# Shruthi-Analog-PoleMixing-v02.net
KiCad netlist of a schematic drawn in EAGLE
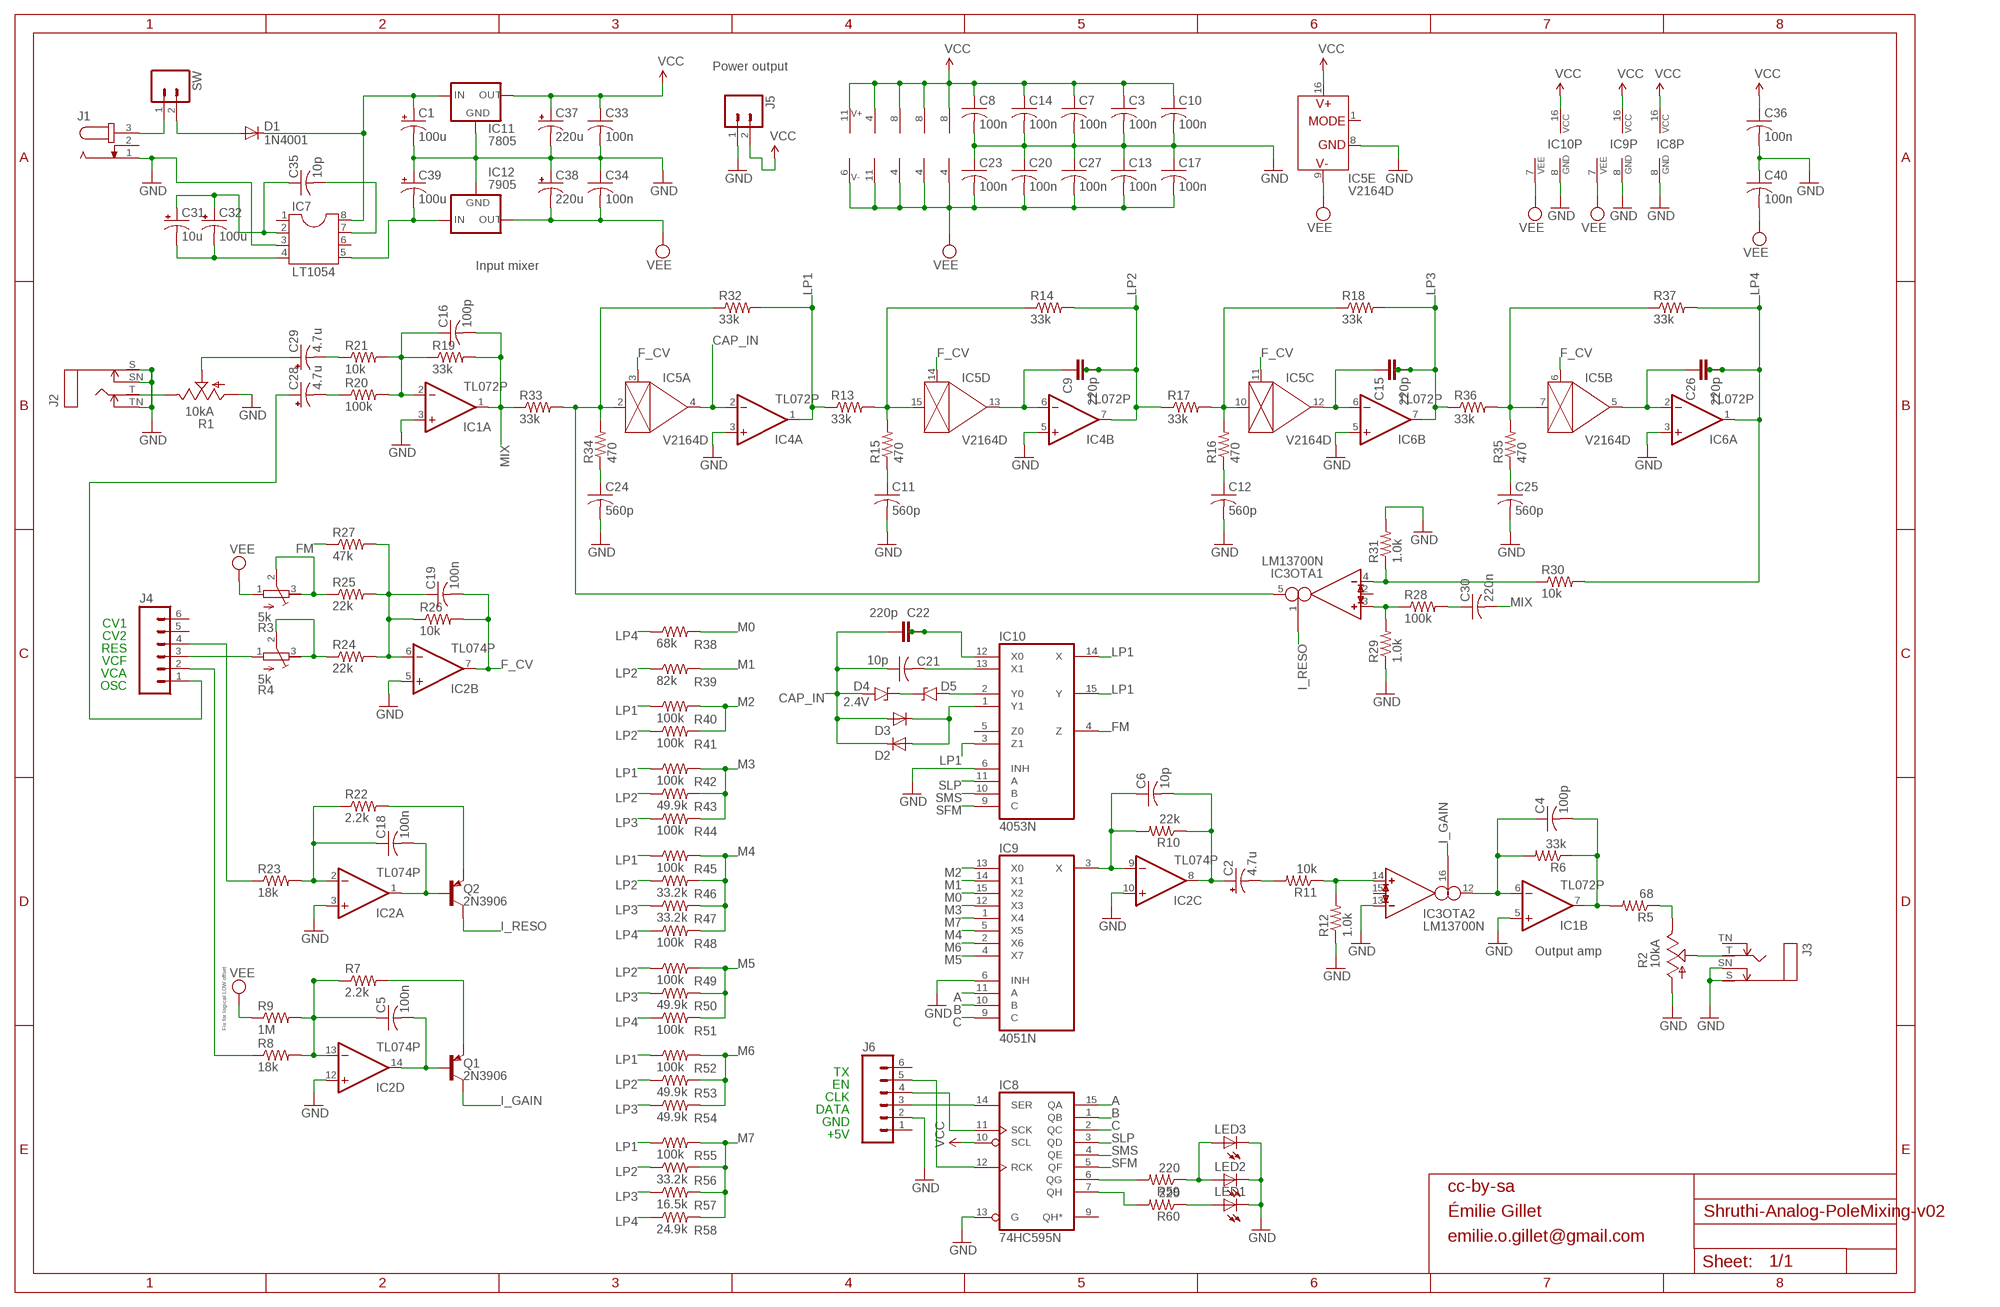
[diagram p0: schematic, sheet 1]

(export (version "E")
  (design (tool "Eeschema 10.0.6"))
  (components
    (comp (ref "C1")
      (value "100u")
      (footprint "eagle-import:E2,5-7")
      (libsource (lib "eagle-import") (part "CPOL-USE2.5-7"))
    )
    (comp (ref "C2")
      (value "4.7u")
      (footprint "eagle-import:E2,5-6")
      (libsource (lib "eagle-import") (part "CPOL-USE2.5-6"))
    )
    (comp (ref "C3")
      (value "100n")
      (footprint "eagle-import:C025-025X050")
      (libsource (lib "eagle-import") (part "C-US025-025X050"))
    )
    (comp (ref "C4")
      (value "100p")
      (footprint "eagle-import:C025-025X050")
      (libsource (lib "eagle-import") (part "C-US025-025X050"))
    )
    (comp (ref "C5")
      (value "100n")
      (footprint "eagle-import:C025-025X050")
      (libsource (lib "eagle-import") (part "C-US025-025X050"))
    )
    (comp (ref "C6")
      (value "10p")
      (footprint "eagle-import:C025-025X050")
      (libsource (lib "eagle-import") (part "C-US025-025X050"))
    )
    (comp (ref "C7")
      (value "100n")
      (footprint "eagle-import:C025-025X050")
      (libsource (lib "eagle-import") (part "C-US025-025X050"))
    )
    (comp (ref "C8")
      (value "100n")
      (footprint "eagle-import:C025-025X050")
      (libsource (lib "eagle-import") (part "C-US025-025X050"))
    )
    (comp (ref "C9")
      (value "220p")
      (footprint "eagle-import:C2.5_5-4")
      (libsource (lib "eagle-import") (part "C-2.5-5/4"))
    )
    (comp (ref "C10")
      (value "100n")
      (footprint "eagle-import:C025-025X050")
      (libsource (lib "eagle-import") (part "C-US025-025X050"))
    )
    (comp (ref "C11")
      (value "560p")
      (footprint "eagle-import:C025-025X050")
      (libsource (lib "eagle-import") (part "C-US025-025X050"))
    )
    (comp (ref "C12")
      (value "560p")
      (footprint "eagle-import:C025-025X050")
      (libsource (lib "eagle-import") (part "C-US025-025X050"))
    )
    (comp (ref "C13")
      (value "100n")
      (footprint "eagle-import:C025-025X050")
      (libsource (lib "eagle-import") (part "C-US025-025X050"))
    )
    (comp (ref "C14")
      (value "100n")
      (footprint "eagle-import:C025-025X050")
      (libsource (lib "eagle-import") (part "C-US025-025X050"))
    )
    (comp (ref "C15")
      (value "220p")
      (footprint "eagle-import:C2.5_5-4")
      (libsource (lib "eagle-import") (part "C-2.5-5/4"))
    )
    (comp (ref "C16")
      (value "100p")
      (footprint "eagle-import:C025-025X050")
      (libsource (lib "eagle-import") (part "C-US025-025X050"))
    )
    (comp (ref "C17")
      (value "100n")
      (footprint "eagle-import:C025-025X050")
      (libsource (lib "eagle-import") (part "C-US025-025X050"))
    )
    (comp (ref "C18")
      (value "100n")
      (footprint "eagle-import:C025-025X050")
      (libsource (lib "eagle-import") (part "C-US025-025X050"))
    )
    (comp (ref "C19")
      (value "100n")
      (footprint "eagle-import:C025-025X050")
      (libsource (lib "eagle-import") (part "C-US025-025X050"))
    )
    (comp (ref "C20")
      (value "100n")
      (footprint "eagle-import:C025-025X050")
      (libsource (lib "eagle-import") (part "C-US025-025X050"))
    )
    (comp (ref "C21")
      (value "10p")
      (footprint "eagle-import:C025-025X050")
      (libsource (lib "eagle-import") (part "C-US025-025X050"))
    )
    (comp (ref "C22")
      (value "220p")
      (footprint "eagle-import:C2.5_5-4")
      (libsource (lib "eagle-import") (part "C-2.5-5/4"))
    )
    (comp (ref "C23")
      (value "100n")
      (footprint "eagle-import:C025-025X050")
      (libsource (lib "eagle-import") (part "C-US025-025X050"))
    )
    (comp (ref "C24")
      (value "560p")
      (footprint "eagle-import:C025-025X050")
      (libsource (lib "eagle-import") (part "C-US025-025X050"))
    )
    (comp (ref "C25")
      (value "560p")
      (footprint "eagle-import:C025-025X050")
      (libsource (lib "eagle-import") (part "C-US025-025X050"))
    )
    (comp (ref "C26")
      (value "220p")
      (footprint "eagle-import:C2.5_5-4")
      (libsource (lib "eagle-import") (part "C-2.5-5/4"))
    )
    (comp (ref "C27")
      (value "100n")
      (footprint "eagle-import:C025-025X050")
      (libsource (lib "eagle-import") (part "C-US025-025X050"))
    )
    (comp (ref "C28")
      (value "4.7u")
      (footprint "eagle-import:E2,5-6")
      (libsource (lib "eagle-import") (part "CPOL-USE2.5-6"))
    )
    (comp (ref "C29")
      (value "4.7u")
      (footprint "eagle-import:E2,5-6")
      (libsource (lib "eagle-import") (part "CPOL-USE2.5-6"))
    )
    (comp (ref "C30")
      (value "220n")
      (footprint "eagle-import:C025-025X050")
      (libsource (lib "eagle-import") (part "C-US025-025X050"))
    )
    (comp (ref "C31")
      (value "10u")
      (footprint "eagle-import:E2,5-5")
      (libsource (lib "eagle-import") (part "CPOL-USE2.5-5"))
    )
    (comp (ref "C32")
      (value "100u")
      (footprint "eagle-import:E2,5-6")
      (libsource (lib "eagle-import") (part "CPOL-USE2.5-6"))
    )
    (comp (ref "C33")
      (value "100n")
      (footprint "eagle-import:C025-025X050")
      (libsource (lib "eagle-import") (part "C-US025-025X050"))
    )
    (comp (ref "C34")
      (value "100n")
      (footprint "eagle-import:C025-025X050")
      (libsource (lib "eagle-import") (part "C-US025-025X050"))
    )
    (comp (ref "C35")
      (value "10p")
      (footprint "eagle-import:C025-025X050")
      (libsource (lib "eagle-import") (part "C-US025-025X050"))
    )
    (comp (ref "C36")
      (value "100n")
      (footprint "eagle-import:C025-025X050")
      (libsource (lib "eagle-import") (part "C-US025-025X050"))
    )
    (comp (ref "C37")
      (value "220u")
      (footprint "eagle-import:E5-10,5")
      (libsource (lib "eagle-import") (part "CPOL-USE5-10.5"))
    )
    (comp (ref "C38")
      (value "220u")
      (footprint "eagle-import:E5-10,5")
      (libsource (lib "eagle-import") (part "CPOL-USE5-10.5"))
    )
    (comp (ref "C39")
      (value "100u")
      (footprint "eagle-import:E2,5-7")
      (libsource (lib "eagle-import") (part "CPOL-USE2.5-7"))
    )
    (comp (ref "C40")
      (value "100n")
      (footprint "eagle-import:C025-025X050")
      (libsource (lib "eagle-import") (part "C-US025-025X050"))
    )
    (comp (ref "D1")
      (value "1N4001")
      (footprint "eagle-import:DO41-10")
      (libsource (lib "eagle-import") (part "1N4004"))
    )
    (comp (ref "D2")
      (value "DIODE-D-5")
      (footprint "eagle-import:D-5")
      (libsource (lib "eagle-import") (part "DIODE-D-5"))
    )
    (comp (ref "D3")
      (value "DIODE-D-5")
      (footprint "eagle-import:D-5")
      (libsource (lib "eagle-import") (part "DIODE-D-5"))
    )
    (comp (ref "D4")
      (value "1N47XXDO35")
      (footprint "eagle-import:D-5")
      (libsource (lib "eagle-import") (part "1N47XXDO35"))
    )
    (comp (ref "D5")
      (value "1N47XXDO35")
      (footprint "eagle-import:D-5")
      (libsource (lib "eagle-import") (part "1N47XXDO35"))
    )
    (comp (ref "IC1")
      (value "TL072P")
      (footprint "eagle-import:DIL08")
      (libsource (lib "eagle-import") (part "TL072P"))
    )
    (comp (ref "IC2")
      (value "TL074P")
      (footprint "eagle-import:DIL14")
      (libsource (lib "eagle-import") (part "TL074P"))
    )
    (comp (ref "IC3")
      (value "LM13700N")
      (footprint "eagle-import:DIL16")
      (libsource (lib "eagle-import") (part "LM13700N"))
    )
    (comp (ref "IC4")
      (value "TL072P")
      (footprint "eagle-import:DIL08")
      (libsource (lib "eagle-import") (part "linear_TL072P"))
    )
    (comp (ref "IC5")
      (value "V2164D")
      (footprint "eagle-import:DIL16")
      (libsource (lib "eagle-import") (part "SSM2164P"))
    )
    (comp (ref "IC6")
      (value "TL072P")
      (footprint "eagle-import:DIL08")
      (libsource (lib "eagle-import") (part "linear_TL072P"))
    )
    (comp (ref "IC7")
      (value "LT1054")
      (footprint "eagle-import:DIL08")
      (libsource (lib "eagle-import") (part "DIL8"))
    )
    (comp (ref "IC8")
      (value "74HC595N")
      (footprint "eagle-import:DIL16")
      (libsource (lib "eagle-import") (part "74595NHC"))
    )
    (comp (ref "IC9")
      (value "4051N")
      (footprint "eagle-import:DIL16")
      (libsource (lib "eagle-import") (part "4051N"))
    )
    (comp (ref "IC10")
      (value "4053N")
      (footprint "eagle-import:DIL16")
      (libsource (lib "eagle-import") (part "4053N"))
    )
    (comp (ref "IC11")
      (value "7805")
      (footprint "eagle-import:78XXS")
      (libsource (lib "eagle-import") (part "78XXS"))
    )
    (comp (ref "IC12")
      (value "7905")
      (footprint "eagle-import:79XXS")
      (libsource (lib "eagle-import") (part "79XXS"))
    )
    (comp (ref "J1")
      (value "JACK-PLUG2")
      (footprint "eagle-import:SPC4078_BIG_HOLES")
      (libsource (lib "eagle-import") (part "JACK-PLUG2"))
    )
    (comp (ref "J2")
      (value "MONOSWS")
      (footprint "eagle-import:NMJ4HC-S")
      (libsource (lib "eagle-import") (part "MONOSWS"))
    )
    (comp (ref "J3")
      (value "MONOSWS")
      (footprint "eagle-import:NMJ4HC-S")
      (libsource (lib "eagle-import") (part "MONOSWS"))
    )
    (comp (ref "J4")
      (value "M06SIP")
      (footprint "eagle-import:1X06")
      (libsource (lib "eagle-import") (part "M06SIP"))
    )
    (comp (ref "J5")
      (value "M02PTH")
      (footprint "eagle-import:1X02")
      (libsource (lib "eagle-import") (part "M02PTH"))
    )
    (comp (ref "J6")
      (value "M06SIP")
      (footprint "eagle-import:1X06")
      (libsource (lib "eagle-import") (part "M06SIP"))
    )
    (comp (ref "LED1")
      (value "LED3MM")
      (footprint "eagle-import:LED3MM")
      (libsource (lib "eagle-import") (part "LED3MM"))
    )
    (comp (ref "LED2")
      (value "LED3MM")
      (footprint "eagle-import:LED3MM")
      (libsource (lib "eagle-import") (part "LED3MM"))
    )
    (comp (ref "LED3")
      (value "LEDCHIP-LED0603")
      (footprint "eagle-import:CHIP-LED0603")
      (libsource (lib "eagle-import") (part "LEDCHIP-LED0603"))
    )
    (comp (ref "Q1")
      (value "2N3906")
      (footprint "eagle-import:TO92-")
      (libsource (lib "eagle-import") (part "2N3906-"))
    )
    (comp (ref "Q2")
      (value "2N3906")
      (footprint "eagle-import:TO92-")
      (libsource (lib "eagle-import") (part "2N3906-"))
    )
    (comp (ref "R1")
      (value "10kA")
      (footprint "eagle-import:CABLE_POT_6MM")
      (libsource (lib "eagle-import") (part "POT_USCABLED"))
    )
    (comp (ref "R2")
      (value "10kA")
      (footprint "eagle-import:CABLE_POT_6MM")
      (libsource (lib "eagle-import") (part "POT_USCABLED"))
    )
    (comp (ref "R3")
      (value "5k")
      (footprint "eagle-import:RTRIM3296X")
      (libsource (lib "eagle-import") (part "R-TRIMM3296X"))
    )
    (comp (ref "R4")
      (value "5k")
      (footprint "eagle-import:RTRIM3296X")
      (libsource (lib "eagle-import") (part "R-TRIMM3296X"))
    )
    (comp (ref "R5")
      (value "68")
      (footprint "eagle-import:0204_7")
      (libsource (lib "eagle-import") (part "R-US_0204/7"))
    )
    (comp (ref "R6")
      (value "33k")
      (footprint "eagle-import:0204_7")
      (libsource (lib "eagle-import") (part "R-US_0204/7"))
    )
    (comp (ref "R7")
      (value "2.2k")
      (footprint "eagle-import:0204_7")
      (libsource (lib "eagle-import") (part "R-US_0204/7"))
    )
    (comp (ref "R8")
      (value "18k")
      (footprint "eagle-import:0204_7")
      (libsource (lib "eagle-import") (part "R-US_0204/7"))
    )
    (comp (ref "R9")
      (value "1M")
      (footprint "eagle-import:0204_7")
      (libsource (lib "eagle-import") (part "R-US_0204/7"))
    )
    (comp (ref "R10")
      (value "22k")
      (footprint "eagle-import:0204_7")
      (libsource (lib "eagle-import") (part "R-US_0204/7"))
    )
    (comp (ref "R11")
      (value "10k")
      (footprint "eagle-import:0204_7")
      (libsource (lib "eagle-import") (part "R-US_0204/7"))
    )
    (comp (ref "R12")
      (value "1.0k")
      (footprint "eagle-import:0204_7")
      (libsource (lib "eagle-import") (part "R-US_0204/7"))
    )
    (comp (ref "R13")
      (value "33k")
      (footprint "eagle-import:0204_7")
      (libsource (lib "eagle-import") (part "R-US_0204/7"))
    )
    (comp (ref "R14")
      (value "33k")
      (footprint "eagle-import:0204_7")
      (libsource (lib "eagle-import") (part "R-US_0204/7"))
    )
    (comp (ref "R15")
      (value "470")
      (footprint "eagle-import:0204_7")
      (libsource (lib "eagle-import") (part "R-US_0204/7"))
    )
    (comp (ref "R16")
      (value "470")
      (footprint "eagle-import:0204_7")
      (libsource (lib "eagle-import") (part "R-US_0204/7"))
    )
    (comp (ref "R17")
      (value "33k")
      (footprint "eagle-import:0204_7")
      (libsource (lib "eagle-import") (part "R-US_0204/7"))
    )
    (comp (ref "R18")
      (value "33k")
      (footprint "eagle-import:0204_7")
      (libsource (lib "eagle-import") (part "R-US_0204/7"))
    )
    (comp (ref "R19")
      (value "33k")
      (footprint "eagle-import:0204_7")
      (libsource (lib "eagle-import") (part "R-US_0204/7"))
    )
    (comp (ref "R20")
      (value "100k")
      (footprint "eagle-import:0204_7")
      (libsource (lib "eagle-import") (part "R-US_0204/7"))
    )
    (comp (ref "R21")
      (value "10k")
      (footprint "eagle-import:0204_7")
      (libsource (lib "eagle-import") (part "R-US_0204/7"))
    )
    (comp (ref "R22")
      (value "2.2k")
      (footprint "eagle-import:0204_7")
      (libsource (lib "eagle-import") (part "R-US_0204/7"))
    )
    (comp (ref "R23")
      (value "18k")
      (footprint "eagle-import:0204_7")
      (libsource (lib "eagle-import") (part "R-US_0204/7"))
    )
    (comp (ref "R24")
      (value "22k")
      (footprint "eagle-import:0204_7")
      (libsource (lib "eagle-import") (part "R-US_0204/7"))
    )
    (comp (ref "R25")
      (value "22k")
      (footprint "eagle-import:0204_7")
      (libsource (lib "eagle-import") (part "R-US_0204/7"))
    )
    (comp (ref "R26")
      (value "10k")
      (footprint "eagle-import:0204_7")
      (libsource (lib "eagle-import") (part "R-US_0204/7"))
    )
    (comp (ref "R27")
      (value "47k")
      (footprint "eagle-import:0204_7")
      (libsource (lib "eagle-import") (part "R-US_0204/7"))
    )
    (comp (ref "R28")
      (value "100k")
      (footprint "eagle-import:0204_7")
      (libsource (lib "eagle-import") (part "R-US_0204/7"))
    )
    (comp (ref "R29")
      (value "1.0k")
      (footprint "eagle-import:0204_7")
      (libsource (lib "eagle-import") (part "R-US_0204/7"))
    )
    (comp (ref "R30")
      (value "10k")
      (footprint "eagle-import:0204_7")
      (libsource (lib "eagle-import") (part "R-US_0204/7"))
    )
    (comp (ref "R31")
      (value "1.0k")
      (footprint "eagle-import:0204_7")
      (libsource (lib "eagle-import") (part "R-US_0204/7"))
    )
    (comp (ref "R32")
      (value "33k")
      (footprint "eagle-import:0204_7")
      (libsource (lib "eagle-import") (part "R-US_0204/7"))
    )
    (comp (ref "R33")
      (value "33k")
      (footprint "eagle-import:0204_7")
      (libsource (lib "eagle-import") (part "R-US_0204/7"))
    )
    (comp (ref "R34")
      (value "470")
      (footprint "eagle-import:0204_7")
      (libsource (lib "eagle-import") (part "R-US_0204/7"))
    )
    (comp (ref "R35")
      (value "470")
      (footprint "eagle-import:0204_7")
      (libsource (lib "eagle-import") (part "R-US_0204/7"))
    )
    (comp (ref "R36")
      (value "33k")
      (footprint "eagle-import:0204_7")
      (libsource (lib "eagle-import") (part "R-US_0204/7"))
    )
    (comp (ref "R37")
      (value "33k")
      (footprint "eagle-import:0204_7")
      (libsource (lib "eagle-import") (part "R-US_0204/7"))
    )
    (comp (ref "R38")
      (value "68k")
      (footprint "eagle-import:0204_7")
      (libsource (lib "eagle-import") (part "R-US_0204/7"))
    )
    (comp (ref "R39")
      (value "82k")
      (footprint "eagle-import:0204_7")
      (libsource (lib "eagle-import") (part "R-US_0204/7"))
    )
    (comp (ref "R40")
      (value "100k")
      (footprint "eagle-import:0204_7")
      (libsource (lib "eagle-import") (part "R-US_0204/7"))
    )
    (comp (ref "R41")
      (value "100k")
      (footprint "eagle-import:0204_7")
      (libsource (lib "eagle-import") (part "R-US_0204/7"))
    )
    (comp (ref "R42")
      (value "100k")
      (footprint "eagle-import:0204_7")
      (libsource (lib "eagle-import") (part "R-US_0204/7"))
    )
    (comp (ref "R43")
      (value "49.9k")
      (footprint "eagle-import:0204_7")
      (libsource (lib "eagle-import") (part "R-US_0204/7"))
    )
    (comp (ref "R44")
      (value "100k")
      (footprint "eagle-import:0204_7")
      (libsource (lib "eagle-import") (part "R-US_0204/7"))
    )
    (comp (ref "R45")
      (value "100k")
      (footprint "eagle-import:0204_7")
      (libsource (lib "eagle-import") (part "R-US_0204/7"))
    )
    (comp (ref "R46")
      (value "33.2k")
      (footprint "eagle-import:0204_7")
      (libsource (lib "eagle-import") (part "R-US_0204/7"))
    )
    (comp (ref "R47")
      (value "33.2k")
      (footprint "eagle-import:0204_7")
      (libsource (lib "eagle-import") (part "R-US_0204/7"))
    )
    (comp (ref "R48")
      (value "100k")
      (footprint "eagle-import:0204_7")
      (libsource (lib "eagle-import") (part "R-US_0204/7"))
    )
    (comp (ref "R49")
      (value "100k")
      (footprint "eagle-import:0204_7")
      (libsource (lib "eagle-import") (part "R-US_0204/7"))
    )
    (comp (ref "R50")
      (value "49.9k")
      (footprint "eagle-import:0204_7")
      (libsource (lib "eagle-import") (part "R-US_0204/7"))
    )
    (comp (ref "R51")
      (value "100k")
      (footprint "eagle-import:0204_7")
      (libsource (lib "eagle-import") (part "R-US_0204/7"))
    )
    (comp (ref "R52")
      (value "100k")
      (footprint "eagle-import:0204_7")
      (libsource (lib "eagle-import") (part "R-US_0204/7"))
    )
    (comp (ref "R53")
      (value "49.9k")
      (footprint "eagle-import:0204_7")
      (libsource (lib "eagle-import") (part "R-US_0204/7"))
    )
    (comp (ref "R54")
      (value "49.9k")
      (footprint "eagle-import:0204_7")
      (libsource (lib "eagle-import") (part "R-US_0204/7"))
    )
    (comp (ref "R55")
      (value "100k")
      (footprint "eagle-import:0204_7")
      (libsource (lib "eagle-import") (part "R-US_0204/7"))
    )
    (comp (ref "R56")
      (value "33.2k")
      (footprint "eagle-import:0204_7")
      (libsource (lib "eagle-import") (part "R-US_0204/7"))
    )
    (comp (ref "R57")
      (value "16.5k")
      (footprint "eagle-import:0204_7")
      (libsource (lib "eagle-import") (part "R-US_0204/7"))
    )
    (comp (ref "R58")
      (value "24.9k")
      (footprint "eagle-import:0204_7")
      (libsource (lib "eagle-import") (part "R-US_0204/7"))
    )
    (comp (ref "R59")
      (value "220")
      (footprint "eagle-import:0204_7")
      (libsource (lib "eagle-import") (part "R-US_0204/7"))
    )
    (comp (ref "R60")
      (value "220")
      (footprint "eagle-import:0204_7")
      (libsource (lib "eagle-import") (part "R-US_0204/7"))
    )
    (comp (ref "SW")
      (value "M02PTH")
      (footprint "eagle-import:1X02")
      (libsource (lib "eagle-import") (part "M02PTH"))
    )
  )
  (nets
    (net (code "1") (name "/A") (class "Default")
      (node (ref "IC8") (pin "15") (pinfunction "QA_15") (pintype "tri_state"))
      (node (ref "IC9") (pin "11") (pinfunction "A_11") (pintype "input"))
    )
    (net (code "2") (name "/B") (class "Default")
      (node (ref "IC8") (pin "1") (pinfunction "QB_1") (pintype "tri_state"))
      (node (ref "IC9") (pin "10") (pinfunction "B_10") (pintype "input"))
    )
    (net (code "3") (name "/C") (class "Default")
      (node (ref "IC8") (pin "2") (pinfunction "QC_2") (pintype "tri_state"))
      (node (ref "IC9") (pin "9") (pinfunction "C_9") (pintype "input"))
    )
    (net (code "4") (name "/CAP_IN") (class "Default")
      (node (ref "C21") (pin "1") (pinfunction "1_1") (pintype "passive"))
      (node (ref "C22") (pin "1") (pinfunction "1_1") (pintype "passive"))
      (node (ref "D2") (pin "C") (pinfunction "C_C") (pintype "passive"))
      (node (ref "D3") (pin "A") (pinfunction "A_A") (pintype "passive"))
      (node (ref "D4") (pin "A") (pinfunction "A_A") (pintype "passive"))
      (node (ref "IC4") (pin "2") (pinfunction "-IN_2") (pintype "input"))
      (node (ref "IC5") (pin "4") (pinfunction "OUT_4") (pintype "output"))
    )
    (net (code "5") (name "/FM") (class "Default")
      (node (ref "IC10") (pin "4") (pinfunction "Z_4") (pintype "bidirectional"))
      (node (ref "R27") (pin "1") (pinfunction "1_1") (pintype "passive"))
    )
    (net (code "6") (name "/F_CV") (class "Default")
      (node (ref "C19") (pin "2") (pinfunction "2_2") (pintype "passive"))
      (node (ref "IC2") (pin "7") (pinfunction "OUT_7") (pintype "output"))
      (node (ref "IC5") (pin "11") (pinfunction "CTRL_11") (pintype "input"))
      (node (ref "IC5") (pin "14") (pinfunction "CTRL_14") (pintype "input"))
      (node (ref "IC5") (pin "3") (pinfunction "CTRL_3") (pintype "input"))
      (node (ref "IC5") (pin "6") (pinfunction "CTRL_6") (pintype "input"))
      (node (ref "R26") (pin "2") (pinfunction "2_2") (pintype "passive"))
    )
    (net (code "7") (name "/I_GAIN") (class "Default")
      (node (ref "IC3") (pin "16") (pinfunction "I_BIAS_16") (pintype "input"))
      (node (ref "Q1") (pin "1") (pinfunction "C_1") (pintype "passive"))
    )
    (net (code "8") (name "/I_RESO") (class "Default")
      (node (ref "IC3") (pin "1") (pinfunction "I_BIAS_1") (pintype "input"))
      (node (ref "Q2") (pin "1") (pinfunction "C_1") (pintype "passive"))
    )
    (net (code "9") (name "/LP1") (class "Default")
      (node (ref "IC10") (pin "14") (pinfunction "X_14") (pintype "bidirectional"))
      (node (ref "IC10") (pin "15") (pinfunction "Y_15") (pintype "bidirectional"))
      (node (ref "IC10") (pin "3") (pinfunction "Z1_3") (pintype "bidirectional"))
      (node (ref "IC4") (pin "1") (pinfunction "OUT_1") (pintype "output"))
      (node (ref "R13") (pin "1") (pinfunction "1_1") (pintype "passive"))
      (node (ref "R32") (pin "2") (pinfunction "2_2") (pintype "passive"))
      (node (ref "R40") (pin "1") (pinfunction "1_1") (pintype "passive"))
      (node (ref "R42") (pin "1") (pinfunction "1_1") (pintype "passive"))
      (node (ref "R45") (pin "1") (pinfunction "1_1") (pintype "passive"))
      (node (ref "R52") (pin "1") (pinfunction "1_1") (pintype "passive"))
      (node (ref "R55") (pin "1") (pinfunction "1_1") (pintype "passive"))
    )
    (net (code "10") (name "/LP2") (class "Default")
      (node (ref "C9") (pin "2") (pinfunction "2_2") (pintype "passive"))
      (node (ref "C9") (pin "3") (pinfunction "3_3") (pintype "passive"))
      (node (ref "IC4") (pin "7") (pinfunction "OUT_7") (pintype "output"))
      (node (ref "R14") (pin "2") (pinfunction "2_2") (pintype "passive"))
      (node (ref "R17") (pin "1") (pinfunction "1_1") (pintype "passive"))
      (node (ref "R39") (pin "1") (pinfunction "1_1") (pintype "passive"))
      (node (ref "R41") (pin "1") (pinfunction "1_1") (pintype "passive"))
      (node (ref "R43") (pin "1") (pinfunction "1_1") (pintype "passive"))
      (node (ref "R46") (pin "1") (pinfunction "1_1") (pintype "passive"))
      (node (ref "R49") (pin "1") (pinfunction "1_1") (pintype "passive"))
      (node (ref "R53") (pin "1") (pinfunction "1_1") (pintype "passive"))
      (node (ref "R56") (pin "1") (pinfunction "1_1") (pintype "passive"))
    )
    (net (code "11") (name "/LP3") (class "Default")
      (node (ref "C15") (pin "2") (pinfunction "2_2") (pintype "passive"))
      (node (ref "C15") (pin "3") (pinfunction "3_3") (pintype "passive"))
      (node (ref "IC6") (pin "7") (pinfunction "OUT_7") (pintype "output"))
      (node (ref "R18") (pin "2") (pinfunction "2_2") (pintype "passive"))
      (node (ref "R36") (pin "1") (pinfunction "1_1") (pintype "passive"))
      (node (ref "R44") (pin "1") (pinfunction "1_1") (pintype "passive"))
      (node (ref "R47") (pin "1") (pinfunction "1_1") (pintype "passive"))
      (node (ref "R50") (pin "1") (pinfunction "1_1") (pintype "passive"))
      (node (ref "R54") (pin "1") (pinfunction "1_1") (pintype "passive"))
      (node (ref "R57") (pin "1") (pinfunction "1_1") (pintype "passive"))
    )
    (net (code "12") (name "/LP4") (class "Default")
      (node (ref "C26") (pin "2") (pinfunction "2_2") (pintype "passive"))
      (node (ref "C26") (pin "3") (pinfunction "3_3") (pintype "passive"))
      (node (ref "IC6") (pin "1") (pinfunction "OUT_1") (pintype "output"))
      (node (ref "R30") (pin "2") (pinfunction "2_2") (pintype "passive"))
      (node (ref "R37") (pin "2") (pinfunction "2_2") (pintype "passive"))
      (node (ref "R38") (pin "1") (pinfunction "1_1") (pintype "passive"))
      (node (ref "R48") (pin "1") (pinfunction "1_1") (pintype "passive"))
      (node (ref "R51") (pin "1") (pinfunction "1_1") (pintype "passive"))
      (node (ref "R58") (pin "1") (pinfunction "1_1") (pintype "passive"))
    )
    (net (code "13") (name "/M0") (class "Default")
      (node (ref "IC9") (pin "15") (pinfunction "X2_15") (pintype "bidirectional"))
      (node (ref "R38") (pin "2") (pinfunction "2_2") (pintype "passive"))
    )
    (net (code "14") (name "/M1") (class "Default")
      (node (ref "IC9") (pin "14") (pinfunction "X1_14") (pintype "bidirectional"))
      (node (ref "R39") (pin "2") (pinfunction "2_2") (pintype "passive"))
    )
    (net (code "15") (name "/M2") (class "Default")
      (node (ref "IC9") (pin "13") (pinfunction "X0_13") (pintype "bidirectional"))
      (node (ref "R40") (pin "2") (pinfunction "2_2") (pintype "passive"))
      (node (ref "R41") (pin "2") (pinfunction "2_2") (pintype "passive"))
    )
    (net (code "16") (name "/M3") (class "Default")
      (node (ref "IC9") (pin "12") (pinfunction "X3_12") (pintype "bidirectional"))
      (node (ref "R42") (pin "2") (pinfunction "2_2") (pintype "passive"))
      (node (ref "R43") (pin "2") (pinfunction "2_2") (pintype "passive"))
      (node (ref "R44") (pin "2") (pinfunction "2_2") (pintype "passive"))
    )
    (net (code "17") (name "/M4") (class "Default")
      (node (ref "IC9") (pin "5") (pinfunction "X5_5") (pintype "bidirectional"))
      (node (ref "R45") (pin "2") (pinfunction "2_2") (pintype "passive"))
      (node (ref "R46") (pin "2") (pinfunction "2_2") (pintype "passive"))
      (node (ref "R47") (pin "2") (pinfunction "2_2") (pintype "passive"))
      (node (ref "R48") (pin "2") (pinfunction "2_2") (pintype "passive"))
    )
    (net (code "18") (name "/M5") (class "Default")
      (node (ref "IC9") (pin "4") (pinfunction "X7_4") (pintype "bidirectional"))
      (node (ref "R49") (pin "2") (pinfunction "2_2") (pintype "passive"))
      (node (ref "R50") (pin "2") (pinfunction "2_2") (pintype "passive"))
      (node (ref "R51") (pin "2") (pinfunction "2_2") (pintype "passive"))
    )
    (net (code "19") (name "/M6") (class "Default")
      (node (ref "IC9") (pin "2") (pinfunction "X6_2") (pintype "bidirectional"))
      (node (ref "R52") (pin "2") (pinfunction "2_2") (pintype "passive"))
      (node (ref "R53") (pin "2") (pinfunction "2_2") (pintype "passive"))
      (node (ref "R54") (pin "2") (pinfunction "2_2") (pintype "passive"))
    )
    (net (code "20") (name "/M7") (class "Default")
      (node (ref "IC9") (pin "1") (pinfunction "X4_1") (pintype "bidirectional"))
      (node (ref "R55") (pin "2") (pinfunction "2_2") (pintype "passive"))
      (node (ref "R56") (pin "2") (pinfunction "2_2") (pintype "passive"))
      (node (ref "R57") (pin "2") (pinfunction "2_2") (pintype "passive"))
      (node (ref "R58") (pin "2") (pinfunction "2_2") (pintype "passive"))
    )
    (net (code "21") (name "/MIX") (class "Default")
      (node (ref "C16") (pin "2") (pinfunction "2_2") (pintype "passive"))
      (node (ref "C30") (pin "2") (pinfunction "2_2") (pintype "passive"))
      (node (ref "IC1") (pin "1") (pinfunction "OUT_1") (pintype "output"))
      (node (ref "R19") (pin "2") (pinfunction "2_2") (pintype "passive"))
      (node (ref "R33") (pin "1") (pinfunction "1_1") (pintype "passive"))
    )
    (net (code "22") (name "/SFM") (class "Default")
      (node (ref "IC10") (pin "9") (pinfunction "C_9") (pintype "input"))
      (node (ref "IC8") (pin "5") (pinfunction "QF_5") (pintype "tri_state"))
    )
    (net (code "23") (name "/SLP") (class "Default")
      (node (ref "IC10") (pin "11") (pinfunction "A_11") (pintype "input"))
      (node (ref "IC8") (pin "3") (pinfunction "QD_3") (pintype "tri_state"))
    )
    (net (code "24") (name "/SMS") (class "Default")
      (node (ref "IC10") (pin "10") (pinfunction "B_10") (pintype "input"))
      (node (ref "IC8") (pin "4") (pinfunction "QE_4") (pintype "tri_state"))
    )
    (net (code "25") (name "GND") (class "Default")
      (node (ref "C1") (pin "-") (pinfunction "-_-") (pintype "passive"))
      (node (ref "C10") (pin "2") (pinfunction "2_2") (pintype "passive"))
      (node (ref "C11") (pin "2") (pinfunction "2_2") (pintype "passive"))
      (node (ref "C12") (pin "2") (pinfunction "2_2") (pintype "passive"))
      (node (ref "C13") (pin "1") (pinfunction "1_1") (pintype "passive"))
      (node (ref "C14") (pin "2") (pinfunction "2_2") (pintype "passive"))
      (node (ref "C17") (pin "1") (pinfunction "1_1") (pintype "passive"))
      (node (ref "C20") (pin "1") (pinfunction "1_1") (pintype "passive"))
      (node (ref "C23") (pin "1") (pinfunction "1_1") (pintype "passive"))
      (node (ref "C24") (pin "2") (pinfunction "2_2") (pintype "passive"))
      (node (ref "C25") (pin "2") (pinfunction "2_2") (pintype "passive"))
      (node (ref "C27") (pin "1") (pinfunction "1_1") (pintype "passive"))
      (node (ref "C3") (pin "2") (pinfunction "2_2") (pintype "passive"))
      (node (ref "C33") (pin "2") (pinfunction "2_2") (pintype "passive"))
      (node (ref "C34") (pin "1") (pinfunction "1_1") (pintype "passive"))
      (node (ref "C36") (pin "2") (pinfunction "2_2") (pintype "passive"))
      (node (ref "C37") (pin "-") (pinfunction "-_-") (pintype "passive"))
      (node (ref "C38") (pin "+") (pinfunction "+_+") (pintype "passive"))
      (node (ref "C39") (pin "+") (pinfunction "+_+") (pintype "passive"))
      (node (ref "C40") (pin "1") (pinfunction "1_1") (pintype "passive"))
      (node (ref "C7") (pin "2") (pinfunction "2_2") (pintype "passive"))
      (node (ref "C8") (pin "2") (pinfunction "2_2") (pintype "passive"))
      (node (ref "IC1") (pin "3") (pinfunction "+IN_3") (pintype "input"))
      (node (ref "IC1") (pin "5") (pinfunction "+IN_5") (pintype "input"))
      (node (ref "IC10") (pin "6") (pinfunction "INH_6") (pintype "input"))
      (node (ref "IC10") (pin "8") (pinfunction "GND_8") (pintype "power_in"))
      (node (ref "IC11") (pin "GND") (pinfunction "GND_GND") (pintype "input"))
      (node (ref "IC12") (pin "GND") (pinfunction "GND_GND") (pintype "input"))
      (node (ref "IC2") (pin "10") (pinfunction "+IN_10") (pintype "input"))
      (node (ref "IC2") (pin "12") (pinfunction "+IN_12") (pintype "input"))
      (node (ref "IC2") (pin "3") (pinfunction "+IN_3") (pintype "input"))
      (node (ref "IC2") (pin "5") (pinfunction "+IN_5") (pintype "input"))
      (node (ref "IC3") (pin "13") (pinfunction "IN_N_13") (pintype "input"))
      (node (ref "IC4") (pin "3") (pinfunction "+IN_3") (pintype "input"))
      (node (ref "IC4") (pin "5") (pinfunction "+IN_5") (pintype "input"))
      (node (ref "IC5") (pin "8") (pinfunction "GND_8") (pintype "power_in"))
      (node (ref "IC6") (pin "3") (pinfunction "+IN_3") (pintype "input"))
      (node (ref "IC6") (pin "5") (pinfunction "+IN_5") (pintype "input"))
      (node (ref "IC7") (pin "3") (pinfunction "3_3") (pintype "passive"))
      (node (ref "IC8") (pin "13") (pinfunction "G_13") (pintype "input"))
      (node (ref "IC8") (pin "8") (pinfunction "GND_8") (pintype "power_in"))
      (node (ref "IC9") (pin "6") (pinfunction "INH_6") (pintype "input"))
      (node (ref "IC9") (pin "8") (pinfunction "GND_8") (pintype "power_in"))
      (node (ref "J1") (pin "1") (pinfunction "1_1") (pintype "passive"))
      (node (ref "J2") (pin "S") (pinfunction "S_S") (pintype "passive"))
      (node (ref "J2") (pin "SN") (pinfunction "SN_SN") (pintype "passive"))
      (node (ref "J2") (pin "TN") (pinfunction "TN_TN") (pintype "passive"))
      (node (ref "J3") (pin "S") (pinfunction "S_S") (pintype "passive"))
      (node (ref "J3") (pin "SN") (pinfunction "SN_SN") (pintype "passive"))
      (node (ref "J5") (pin "1") (pinfunction "1_1") (pintype "passive"))
      (node (ref "J6") (pin "2") (pinfunction "2_2") (pintype "passive"))
      (node (ref "LED1") (pin "K") (pinfunction "C_K") (pintype "passive"))
      (node (ref "LED2") (pin "K") (pinfunction "C_K") (pintype "passive"))
      (node (ref "LED3") (pin "C") (pinfunction "C_C") (pintype "passive"))
      (node (ref "R1") (pin "A") (pinfunction "A_A") (pintype "passive"))
      (node (ref "R12") (pin "1") (pinfunction "1_1") (pintype "passive"))
      (node (ref "R2") (pin "A") (pinfunction "A_A") (pintype "passive"))
      (node (ref "R29") (pin "1") (pinfunction "1_1") (pintype "passive"))
      (node (ref "R31") (pin "2") (pinfunction "2_2") (pintype "passive"))
    )
    (net (code "26") (name "Net-(C1-Pad+)") (class "Default")
      (node (ref "C1") (pin "+") (pinfunction "+_+") (pintype "passive"))
      (node (ref "D1") (pin "C") (pinfunction "C_C") (pintype "passive"))
      (node (ref "IC11") (pin "IN") (pinfunction "IN_IN") (pintype "input"))
      (node (ref "IC7") (pin "8") (pinfunction "8_8") (pintype "passive"))
    )
    (net (code "27") (name "Net-(C2-Pad-)") (class "Default")
      (node (ref "C2") (pin "-") (pinfunction "-_-") (pintype "passive"))
      (node (ref "R11") (pin "2") (pinfunction "2_2") (pintype "passive"))
    )
    (net (code "28") (name "Net-(C11-Pad1)") (class "Default")
      (node (ref "C11") (pin "1") (pinfunction "1_1") (pintype "passive"))
      (node (ref "R15") (pin "1") (pinfunction "1_1") (pintype "passive"))
    )
    (net (code "29") (name "Net-(C12-Pad1)") (class "Default")
      (node (ref "C12") (pin "1") (pinfunction "1_1") (pintype "passive"))
      (node (ref "R16") (pin "1") (pinfunction "1_1") (pintype "passive"))
    )
    (net (code "30") (name "Net-(C24-Pad1)") (class "Default")
      (node (ref "C24") (pin "1") (pinfunction "1_1") (pintype "passive"))
      (node (ref "R34") (pin "1") (pinfunction "1_1") (pintype "passive"))
    )
    (net (code "31") (name "Net-(C25-Pad1)") (class "Default")
      (node (ref "C25") (pin "1") (pinfunction "1_1") (pintype "passive"))
      (node (ref "R35") (pin "1") (pinfunction "1_1") (pintype "passive"))
    )
    (net (code "32") (name "Net-(C28-Pad+)") (class "Default")
      (node (ref "C28") (pin "+") (pinfunction "+_+") (pintype "passive"))
      (node (ref "J4") (pin "1") (pinfunction "1_1") (pintype "passive"))
    )
    (net (code "33") (name "Net-(C28-Pad-)") (class "Default")
      (node (ref "C28") (pin "-") (pinfunction "-_-") (pintype "passive"))
      (node (ref "R20") (pin "1") (pinfunction "1_1") (pintype "passive"))
    )
    (net (code "34") (name "Net-(C29-Pad+)") (class "Default")
      (node (ref "C29") (pin "+") (pinfunction "+_+") (pintype "passive"))
      (node (ref "R1") (pin "S") (pinfunction "S_S") (pintype "passive"))
    )
    (net (code "35") (name "Net-(C29-Pad-)") (class "Default")
      (node (ref "C29") (pin "-") (pinfunction "-_-") (pintype "passive"))
      (node (ref "R21") (pin "1") (pinfunction "1_1") (pintype "passive"))
    )
    (net (code "36") (name "Net-(C30-Pad1)") (class "Default")
      (node (ref "C30") (pin "1") (pinfunction "1_1") (pintype "passive"))
      (node (ref "R28") (pin "2") (pinfunction "2_2") (pintype "passive"))
    )
    (net (code "37") (name "Net-(C31-Pad+)") (class "Default")
      (node (ref "C31") (pin "+") (pinfunction "+_+") (pintype "passive"))
      (node (ref "C32") (pin "+") (pinfunction "+_+") (pintype "passive"))
      (node (ref "C35") (pin "1") (pinfunction "1_1") (pintype "passive"))
      (node (ref "IC7") (pin "2") (pinfunction "2_2") (pintype "passive"))
    )
    (net (code "38") (name "Net-(C31-Pad-)") (class "Default")
      (node (ref "C31") (pin "-") (pinfunction "-_-") (pintype "passive"))
      (node (ref "C32") (pin "-") (pinfunction "-_-") (pintype "passive"))
      (node (ref "IC7") (pin "4") (pinfunction "4_4") (pintype "passive"))
    )
    (net (code "39") (name "Net-(C35-Pad2)") (class "Default")
      (node (ref "C35") (pin "2") (pinfunction "2_2") (pintype "passive"))
      (node (ref "IC7") (pin "7") (pinfunction "7_7") (pintype "passive"))
    )
    (net (code "40") (name "Net-(C39-Pad-)") (class "Default")
      (node (ref "C39") (pin "-") (pinfunction "-_-") (pintype "passive"))
      (node (ref "IC12") (pin "IN") (pinfunction "IN_IN") (pintype "input"))
      (node (ref "IC7") (pin "5") (pinfunction "5_5") (pintype "passive"))
    )
    (net (code "41") (name "Net-(D1-PadA)") (class "Default")
      (node (ref "D1") (pin "A") (pinfunction "A_A") (pintype "passive"))
      (node (ref "SW") (pin "2") (pinfunction "2_2") (pintype "passive"))
    )
    (net (code "42") (name "Net-(D4-PadC)") (class "Default")
      (node (ref "D4") (pin "C") (pinfunction "C_C") (pintype "passive"))
      (node (ref "D5") (pin "C") (pinfunction "C_C") (pintype "passive"))
    )
    (net (code "43") (name "Net-(IC1A--IN)") (class "Default")
      (node (ref "C16") (pin "1") (pinfunction "1_1") (pintype "passive"))
      (node (ref "IC1") (pin "2") (pinfunction "-IN_2") (pintype "input"))
      (node (ref "R19") (pin "1") (pinfunction "1_1") (pintype "passive"))
      (node (ref "R20") (pin "2") (pinfunction "2_2") (pintype "passive"))
      (node (ref "R21") (pin "2") (pinfunction "2_2") (pintype "passive"))
    )
    (net (code "44") (name "Net-(IC1B--IN)") (class "Default")
      (node (ref "C4") (pin "1") (pinfunction "1_1") (pintype "passive"))
      (node (ref "IC1") (pin "6") (pinfunction "-IN_6") (pintype "input"))
      (node (ref "IC3") (pin "12") (pinfunction "OUT_12") (pintype "output"))
      (node (ref "R6") (pin "2") (pinfunction "2_2") (pintype "passive"))
    )
    (net (code "45") (name "Net-(IC1B-OUT)") (class "Default")
      (node (ref "C4") (pin "2") (pinfunction "2_2") (pintype "passive"))
      (node (ref "IC1") (pin "7") (pinfunction "OUT_7") (pintype "output"))
      (node (ref "R5") (pin "2") (pinfunction "2_2") (pintype "passive"))
      (node (ref "R6") (pin "1") (pinfunction "1_1") (pintype "passive"))
    )
    (net (code "46") (name "Net-(IC2A--IN)") (class "Default")
      (node (ref "C18") (pin "1") (pinfunction "1_1") (pintype "passive"))
      (node (ref "IC2") (pin "2") (pinfunction "-IN_2") (pintype "input"))
      (node (ref "R22") (pin "1") (pinfunction "1_1") (pintype "passive"))
      (node (ref "R23") (pin "2") (pinfunction "2_2") (pintype "passive"))
    )
    (net (code "47") (name "Net-(IC2A-OUT)") (class "Default")
      (node (ref "C18") (pin "2") (pinfunction "2_2") (pintype "passive"))
      (node (ref "IC2") (pin "1") (pinfunction "OUT_1") (pintype "output"))
      (node (ref "Q2") (pin "2") (pinfunction "B_2") (pintype "passive"))
    )
    (net (code "48") (name "Net-(IC2B--IN)") (class "Default")
      (node (ref "C19") (pin "1") (pinfunction "1_1") (pintype "passive"))
      (node (ref "IC2") (pin "6") (pinfunction "-IN_6") (pintype "input"))
      (node (ref "R24") (pin "2") (pinfunction "2_2") (pintype "passive"))
      (node (ref "R25") (pin "2") (pinfunction "2_2") (pintype "passive"))
      (node (ref "R26") (pin "1") (pinfunction "1_1") (pintype "passive"))
      (node (ref "R27") (pin "2") (pinfunction "2_2") (pintype "passive"))
    )
    (net (code "49") (name "Net-(IC2C--IN)") (class "Default")
      (node (ref "C6") (pin "1") (pinfunction "1_1") (pintype "passive"))
      (node (ref "IC2") (pin "9") (pinfunction "-IN_9") (pintype "input"))
      (node (ref "IC9") (pin "3") (pinfunction "X_3") (pintype "bidirectional"))
      (node (ref "R10") (pin "2") (pinfunction "2_2") (pintype "passive"))
    )
    (net (code "50") (name "Net-(IC2C-OUT)") (class "Default")
      (node (ref "C2") (pin "+") (pinfunction "+_+") (pintype "passive"))
      (node (ref "C6") (pin "2") (pinfunction "2_2") (pintype "passive"))
      (node (ref "IC2") (pin "8") (pinfunction "OUT_8") (pintype "output"))
      (node (ref "R10") (pin "1") (pinfunction "1_1") (pintype "passive"))
    )
    (net (code "51") (name "Net-(IC2D--IN)") (class "Default")
      (node (ref "C5") (pin "1") (pinfunction "1_1") (pintype "passive"))
      (node (ref "IC2") (pin "13") (pinfunction "-IN_13") (pintype "input"))
      (node (ref "R7") (pin "1") (pinfunction "1_1") (pintype "passive"))
      (node (ref "R8") (pin "2") (pinfunction "2_2") (pintype "passive"))
      (node (ref "R9") (pin "2") (pinfunction "2_2") (pintype "passive"))
    )
    (net (code "52") (name "Net-(IC2D-OUT)") (class "Default")
      (node (ref "C5") (pin "2") (pinfunction "2_2") (pintype "passive"))
      (node (ref "IC2") (pin "14") (pinfunction "OUT_14") (pintype "output"))
      (node (ref "Q1") (pin "2") (pinfunction "B_2") (pintype "passive"))
    )
    (net (code "53") (name "Net-(IC3C-IN_N)") (class "Default")
      (node (ref "IC3") (pin "4") (pinfunction "IN_N_4") (pintype "input"))
      (node (ref "R30") (pin "1") (pinfunction "1_1") (pintype "passive"))
      (node (ref "R31") (pin "1") (pinfunction "1_1") (pintype "passive"))
    )
    (net (code "54") (name "Net-(IC3C-IN_P)") (class "Default")
      (node (ref "IC3") (pin "3") (pinfunction "IN_P_3") (pintype "input"))
      (node (ref "R28") (pin "1") (pinfunction "1_1") (pintype "passive"))
      (node (ref "R29") (pin "2") (pinfunction "2_2") (pintype "passive"))
    )
    (net (code "55") (name "Net-(IC3C-OUT)") (class "Default")
      (node (ref "IC3") (pin "5") (pinfunction "OUT_5") (pintype "output"))
      (node (ref "IC5") (pin "2") (pinfunction "IN_2") (pintype "input"))
      (node (ref "R32") (pin "1") (pinfunction "1_1") (pintype "passive"))
      (node (ref "R33") (pin "2") (pinfunction "2_2") (pintype "passive"))
      (node (ref "R34") (pin "2") (pinfunction "2_2") (pintype "passive"))
    )
    (net (code "56") (name "Net-(IC3D-IN_P)") (class "Default")
      (node (ref "IC3") (pin "14") (pinfunction "IN_P_14") (pintype "input"))
      (node (ref "R11") (pin "1") (pinfunction "1_1") (pintype "passive"))
      (node (ref "R12") (pin "2") (pinfunction "2_2") (pintype "passive"))
    )
    (net (code "57") (name "Net-(IC4B--IN)") (class "Default")
      (node (ref "C9") (pin "1") (pinfunction "1_1") (pintype "passive"))
      (node (ref "IC4") (pin "6") (pinfunction "-IN_6") (pintype "input"))
      (node (ref "IC5") (pin "13") (pinfunction "OUT_13") (pintype "output"))
    )
    (net (code "58") (name "Net-(IC5B-IN)") (class "Default")
      (node (ref "IC5") (pin "7") (pinfunction "IN_7") (pintype "input"))
      (node (ref "R35") (pin "2") (pinfunction "2_2") (pintype "passive"))
      (node (ref "R36") (pin "2") (pinfunction "2_2") (pintype "passive"))
      (node (ref "R37") (pin "1") (pinfunction "1_1") (pintype "passive"))
    )
    (net (code "59") (name "Net-(IC5B-OUT)") (class "Default")
      (node (ref "C26") (pin "1") (pinfunction "1_1") (pintype "passive"))
      (node (ref "IC5") (pin "5") (pinfunction "OUT_5") (pintype "output"))
      (node (ref "IC6") (pin "2") (pinfunction "-IN_2") (pintype "input"))
    )
    (net (code "60") (name "Net-(IC5C-IN)") (class "Default")
      (node (ref "IC5") (pin "10") (pinfunction "IN_10") (pintype "input"))
      (node (ref "R16") (pin "2") (pinfunction "2_2") (pintype "passive"))
      (node (ref "R17") (pin "2") (pinfunction "2_2") (pintype "passive"))
      (node (ref "R18") (pin "1") (pinfunction "1_1") (pintype "passive"))
    )
    (net (code "61") (name "Net-(IC5C-OUT)") (class "Default")
      (node (ref "C15") (pin "1") (pinfunction "1_1") (pintype "passive"))
      (node (ref "IC5") (pin "12") (pinfunction "OUT_12") (pintype "output"))
      (node (ref "IC6") (pin "6") (pinfunction "-IN_6") (pintype "input"))
    )
    (net (code "62") (name "Net-(IC5D-IN)") (class "Default")
      (node (ref "IC5") (pin "15") (pinfunction "IN_15") (pintype "input"))
      (node (ref "R13") (pin "2") (pinfunction "2_2") (pintype "passive"))
      (node (ref "R14") (pin "1") (pinfunction "1_1") (pintype "passive"))
      (node (ref "R15") (pin "2") (pinfunction "2_2") (pintype "passive"))
    )
    (net (code "63") (name "Net-(IC8A-QG)") (class "Default")
      (node (ref "IC8") (pin "6") (pinfunction "QG_6") (pintype "tri_state"))
      (node (ref "R59") (pin "2") (pinfunction "2_2") (pintype "passive"))
    )
    (net (code "64") (name "Net-(IC8A-QH)") (class "Default")
      (node (ref "IC8") (pin "7") (pinfunction "QH_7") (pintype "tri_state"))
      (node (ref "R60") (pin "2") (pinfunction "2_2") (pintype "passive"))
    )
    (net (code "65") (name "Net-(IC8A-RCK)") (class "Default")
      (node (ref "IC8") (pin "12") (pinfunction "RCK_12") (pintype "input"))
      (node (ref "J6") (pin "5") (pinfunction "5_5") (pintype "passive"))
    )
    (net (code "66") (name "Net-(IC8A-SCK)") (class "Default")
      (node (ref "IC8") (pin "11") (pinfunction "SCK_11") (pintype "input"))
      (node (ref "J6") (pin "4") (pinfunction "4_4") (pintype "passive"))
    )
    (net (code "67") (name "Net-(IC8A-SER)") (class "Default")
      (node (ref "IC8") (pin "14") (pinfunction "SER_14") (pintype "input"))
      (node (ref "J6") (pin "3") (pinfunction "3_3") (pintype "passive"))
    )
    (net (code "68") (name "Net-(IC10A-X0)") (class "Default")
      (node (ref "C22") (pin "2") (pinfunction "2_2") (pintype "passive"))
      (node (ref "C22") (pin "3") (pinfunction "3_3") (pintype "passive"))
      (node (ref "IC10") (pin "12") (pinfunction "X0_12") (pintype "bidirectional"))
    )
    (net (code "69") (name "Net-(IC10A-X1)") (class "Default")
      (node (ref "C21") (pin "2") (pinfunction "2_2") (pintype "passive"))
      (node (ref "IC10") (pin "13") (pinfunction "X1_13") (pintype "bidirectional"))
    )
    (net (code "70") (name "Net-(IC10A-Y0)") (class "Default")
      (node (ref "D5") (pin "A") (pinfunction "A_A") (pintype "passive"))
      (node (ref "IC10") (pin "2") (pinfunction "Y0_2") (pintype "bidirectional"))
    )
    (net (code "71") (name "Net-(IC10A-Y1)") (class "Default")
      (node (ref "D2") (pin "A") (pinfunction "A_A") (pintype "passive"))
      (node (ref "D3") (pin "C") (pinfunction "C_C") (pintype "passive"))
      (node (ref "IC10") (pin "1") (pinfunction "Y1_1") (pintype "bidirectional"))
    )
    (net (code "72") (name "Net-(J1-Pad3)") (class "Default")
      (node (ref "J1") (pin "3") (pinfunction "3_3") (pintype "passive"))
      (node (ref "SW") (pin "1") (pinfunction "1_1") (pintype "passive"))
    )
    (net (code "73") (name "Net-(J2-PadT)") (class "Default")
      (node (ref "J2") (pin "T") (pinfunction "T_T") (pintype "passive"))
      (node (ref "R1") (pin "E") (pinfunction "E_E") (pintype "passive"))
    )
    (net (code "74") (name "Net-(J3-PadT)") (class "Default")
      (node (ref "J3") (pin "T") (pinfunction "T_T") (pintype "passive"))
      (node (ref "R2") (pin "S") (pinfunction "S_S") (pintype "passive"))
    )
    (net (code "75") (name "Net-(J4-Pad2)") (class "Default")
      (node (ref "J4") (pin "2") (pinfunction "2_2") (pintype "passive"))
      (node (ref "R8") (pin "1") (pinfunction "1_1") (pintype "passive"))
    )
    (net (code "76") (name "Net-(J4-Pad4)") (class "Default")
      (node (ref "J4") (pin "4") (pinfunction "4_4") (pintype "passive"))
      (node (ref "R23") (pin "1") (pinfunction "1_1") (pintype "passive"))
    )
    (net (code "77") (name "Net-(LED1-PadA)") (class "Default")
      (node (ref "LED1") (pin "A") (pinfunction "A_A") (pintype "passive"))
      (node (ref "R60") (pin "1") (pinfunction "1_1") (pintype "passive"))
    )
    (net (code "78") (name "Net-(LED2-PadA)") (class "Default")
      (node (ref "LED2") (pin "A") (pinfunction "A_A") (pintype "passive"))
      (node (ref "LED3") (pin "A") (pinfunction "A_A") (pintype "passive"))
      (node (ref "R59") (pin "1") (pinfunction "1_1") (pintype "passive"))
    )
    (net (code "79") (name "Net-(Q1-E)") (class "Default")
      (node (ref "Q1") (pin "3") (pinfunction "E_3") (pintype "passive"))
      (node (ref "R7") (pin "2") (pinfunction "2_2") (pintype "passive"))
    )
    (net (code "80") (name "Net-(Q2-E)") (class "Default")
      (node (ref "Q2") (pin "3") (pinfunction "E_3") (pintype "passive"))
      (node (ref "R22") (pin "2") (pinfunction "2_2") (pintype "passive"))
    )
    (net (code "81") (name "Net-(R2-PadE)") (class "Default")
      (node (ref "R2") (pin "E") (pinfunction "E_E") (pintype "passive"))
      (node (ref "R5") (pin "1") (pinfunction "1_1") (pintype "passive"))
    )
    (net (code "82") (name "Net-(R3-A)") (class "Default")
      (node (ref "R25") (pin "1") (pinfunction "1_1") (pintype "passive"))
      (node (ref "R3") (pin "2") (pinfunction "S_2") (pintype "passive"))
      (node (ref "R3") (pin "3") (pinfunction "A_3") (pintype "passive"))
    )
    (net (code "83") (name "Net-(R4-A)") (class "Default")
      (node (ref "R24") (pin "1") (pinfunction "1_1") (pintype "passive"))
      (node (ref "R4") (pin "2") (pinfunction "S_2") (pintype "passive"))
      (node (ref "R4") (pin "3") (pinfunction "A_3") (pintype "passive"))
    )
    (net (code "84") (name "Net-(R4-E)") (class "Default")
      (node (ref "J4") (pin "3") (pinfunction "3_3") (pintype "passive"))
      (node (ref "R4") (pin "1") (pinfunction "E_1") (pintype "passive"))
    )
    (net (code "85") (name "VCC") (class "Default")
      (node (ref "C10") (pin "1") (pinfunction "1_1") (pintype "passive"))
      (node (ref "C14") (pin "1") (pinfunction "1_1") (pintype "passive"))
      (node (ref "C3") (pin "1") (pinfunction "1_1") (pintype "passive"))
      (node (ref "C33") (pin "1") (pinfunction "1_1") (pintype "passive"))
      (node (ref "C36") (pin "1") (pinfunction "1_1") (pintype "passive"))
      (node (ref "C37") (pin "+") (pinfunction "+_+") (pintype "passive"))
      (node (ref "C7") (pin "1") (pinfunction "1_1") (pintype "passive"))
      (node (ref "C8") (pin "1") (pinfunction "1_1") (pintype "passive"))
      (node (ref "IC1") (pin "8") (pinfunction "V+_8") (pintype "power_in"))
      (node (ref "IC10") (pin "16") (pinfunction "VCC_16") (pintype "power_in"))
      (node (ref "IC11") (pin "OUT") (pinfunction "OUT_OUT") (pintype "passive"))
      (node (ref "IC2") (pin "4") (pinfunction "V+_4") (pintype "power_in"))
      (node (ref "IC3") (pin "11") (pinfunction "V+_11") (pintype "power_in"))
      (node (ref "IC4") (pin "8") (pinfunction "V+_8") (pintype "power_in"))
      (node (ref "IC5") (pin "16") (pinfunction "V+_16") (pintype "power_in"))
      (node (ref "IC6") (pin "8") (pinfunction "V+_8") (pintype "power_in"))
      (node (ref "IC8") (pin "10") (pinfunction "SCL_10") (pintype "input"))
      (node (ref "IC8") (pin "16") (pinfunction "VCC_16") (pintype "power_in"))
      (node (ref "IC9") (pin "16") (pinfunction "VCC_16") (pintype "power_in"))
      (node (ref "J5") (pin "2") (pinfunction "2_2") (pintype "passive"))
    )
    (net (code "86") (name "VEE") (class "Default")
      (node (ref "C13") (pin "2") (pinfunction "2_2") (pintype "passive"))
      (node (ref "C17") (pin "2") (pinfunction "2_2") (pintype "passive"))
      (node (ref "C20") (pin "2") (pinfunction "2_2") (pintype "passive"))
      (node (ref "C23") (pin "2") (pinfunction "2_2") (pintype "passive"))
      (node (ref "C27") (pin "2") (pinfunction "2_2") (pintype "passive"))
      (node (ref "C34") (pin "2") (pinfunction "2_2") (pintype "passive"))
      (node (ref "C38") (pin "-") (pinfunction "-_-") (pintype "passive"))
      (node (ref "C40") (pin "2") (pinfunction "2_2") (pintype "passive"))
      (node (ref "IC1") (pin "4") (pinfunction "V-_4") (pintype "power_in"))
      (node (ref "IC10") (pin "7") (pinfunction "VEE_7") (pintype "power_in"))
      (node (ref "IC12") (pin "OUT") (pinfunction "OUT_OUT") (pintype "passive"))
      (node (ref "IC2") (pin "11") (pinfunction "V-_11") (pintype "power_in"))
      (node (ref "IC3") (pin "6") (pinfunction "V-_6") (pintype "power_in"))
      (node (ref "IC4") (pin "4") (pinfunction "V-_4") (pintype "power_in"))
      (node (ref "IC5") (pin "9") (pinfunction "V-_9") (pintype "power_in"))
      (node (ref "IC6") (pin "4") (pinfunction "V-_4") (pintype "power_in"))
      (node (ref "IC9") (pin "7") (pinfunction "VEE_7") (pintype "power_in"))
      (node (ref "R3") (pin "1") (pinfunction "E_1") (pintype "passive"))
      (node (ref "R9") (pin "1") (pinfunction "1_1") (pintype "passive"))
    )
    (net (code "87") (name "unconnected-(IC3C-I_DIODE-Pad2)") (class "Default")
      (node (ref "IC3") (pin "2") (pinfunction "I_DIODE_2") (pintype "input"))
    )
    (net (code "88") (name "unconnected-(IC3D-I_DIODE-Pad15)") (class "Default")
      (node (ref "IC3") (pin "15") (pinfunction "I_DIODE_15") (pintype "input"))
    )
    (net (code "89") (name "unconnected-(IC5E-MODE-Pad1)") (class "Default")
      (node (ref "IC5") (pin "1") (pinfunction "MODE_1") (pintype "input"))
    )
    (net (code "90") (name "unconnected-(IC7-Pad1)") (class "Default")
      (node (ref "IC7") (pin "1") (pinfunction "1_1") (pintype "passive"))
    )
    (net (code "91") (name "unconnected-(IC7-Pad6)") (class "Default")
      (node (ref "IC7") (pin "6") (pinfunction "6_6") (pintype "passive"))
    )
    (net (code "92") (name "unconnected-(IC8A-QH*-Pad9)") (class "Default")
      (node (ref "IC8") (pin "9") (pinfunction "QH*_9") (pintype "tri_state"))
    )
    (net (code "93") (name "unconnected-(IC10A-Z0-Pad5)") (class "Default")
      (node (ref "IC10") (pin "5") (pinfunction "Z0_5") (pintype "bidirectional"))
    )
    (net (code "94") (name "unconnected-(J1-Pad2)") (class "Default")
      (node (ref "J1") (pin "2") (pinfunction "2_2") (pintype "passive"))
    )
    (net (code "95") (name "unconnected-(J3-PadTN)") (class "Default")
      (node (ref "J3") (pin "TN") (pinfunction "TN_TN") (pintype "passive"))
    )
    (net (code "96") (name "unconnected-(J4-Pad5)") (class "Default")
      (node (ref "J4") (pin "5") (pinfunction "5_5") (pintype "passive"))
    )
    (net (code "97") (name "unconnected-(J4-Pad6)") (class "Default")
      (node (ref "J4") (pin "6") (pinfunction "6_6") (pintype "passive"))
    )
    (net (code "98") (name "unconnected-(J6-Pad1)") (class "Default")
      (node (ref "J6") (pin "1") (pinfunction "1_1") (pintype "passive"))
    )
    (net (code "99") (name "unconnected-(J6-Pad6)") (class "Default")
      (node (ref "J6") (pin "6") (pinfunction "6_6") (pintype "passive"))
    )
  )
)
